# commu.net
KiCad netlist of a schematic drawn in Altium Designer
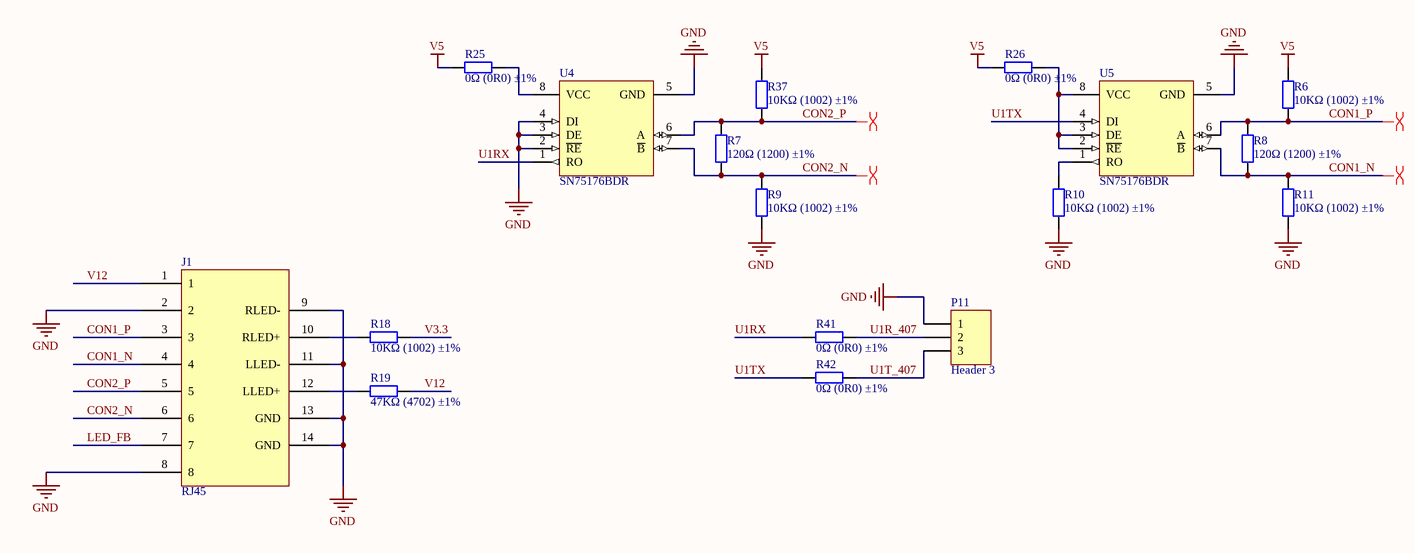
[diagram p0: commu.SchDoc]

(export (version "E")
  (design (tool "Eeschema 10.0.6"))
  (components
    (comp (ref "J1") (value "RJ45") (footprint "RJ45_1") (libsource (lib "CHK-I") (part "RJ45_1")))
    (comp (ref "P11")
      (value "Header 3")
      (footprint "HDR1X3")
      (description "Header, 3-Pin")
      (fields (field (name "PUBLISHER") "Altium Limited"))
      (libsource (lib "Miscellaneous Connectors") (part "Header 3"))
    )
    (comp (ref "R6")
      (value "10KΩ (1002) ±1%")
      (footprint "0603_R")
      (description "贴片电阻")
      (libsource (lib "Miscellaneous Devices LC") (part "0603 10KΩ (1002) 1%"))
    )
    (comp (ref "R7")
      (value "120Ω (1200) ±1%")
      (footprint "0603_R")
      (description "贴片电阻")
      (libsource (lib "Miscellaneous Devices LC") (part "0603 120Ω (1200) 1%"))
    )
    (comp (ref "R8")
      (value "120Ω (1200) ±1%")
      (footprint "0603_R")
      (description "贴片电阻")
      (libsource (lib "Miscellaneous Devices LC") (part "0603 120Ω (1200) 1%"))
    )
    (comp (ref "R9")
      (value "10KΩ (1002) ±1%")
      (footprint "0603_R")
      (description "贴片电阻")
      (libsource (lib "Miscellaneous Devices LC") (part "0603 10KΩ (1002) 1%"))
    )
    (comp (ref "R10")
      (value "10KΩ (1002) ±1%")
      (footprint "0603_R")
      (description "贴片电阻")
      (libsource (lib "Miscellaneous Devices LC") (part "0603 10KΩ (1002) 1%"))
    )
    (comp (ref "R11")
      (value "10KΩ (1002) ±1%")
      (footprint "0603_R")
      (description "贴片电阻")
      (libsource (lib "Miscellaneous Devices LC") (part "0603 10KΩ (1002) 1%"))
    )
    (comp (ref "R18")
      (value "10KΩ (1002) ±1%")
      (footprint "0603_R")
      (description "贴片电阻")
      (libsource (lib "") (part "0603 10KΩ (1002) 1%_1"))
    )
    (comp (ref "R19")
      (value "47KΩ (4702) ±1%")
      (footprint "0603_R")
      (description "贴片电阻")
      (libsource (lib "Miscellaneous Devices LC") (part "0603 47KΩ (4702) 1%"))
    )
    (comp (ref "R25")
      (value "0Ω (0R0) ±1%")
      (footprint "1206_R")
      (description "贴片电阻")
      (libsource (lib "Miscellaneous Devices LC") (part "1206 0Ω (0R0) 1%"))
    )
    (comp (ref "R26")
      (value "0Ω (0R0) ±1%")
      (footprint "1206_R")
      (description "贴片电阻")
      (libsource (lib "Miscellaneous Devices LC") (part "1206 0Ω (0R0) 1%"))
    )
    (comp (ref "R37")
      (value "10KΩ (1002) ±1%")
      (footprint "0603_R")
      (description "贴片电阻")
      (libsource (lib "Miscellaneous Devices LC") (part "0603 10KΩ (1002) 1%"))
    )
    (comp (ref "R41")
      (value "0Ω (0R0) ±1%")
      (footprint "0603_R")
      (description "贴片电阻")
      (libsource (lib "Miscellaneous Devices LC") (part "0603 0Ω (0R0) 1%"))
    )
    (comp (ref "R42")
      (value "0Ω (0R0) ±1%")
      (footprint "0603_R")
      (description "贴片电阻")
      (libsource (lib "Miscellaneous Devices LC") (part "0603 0Ω (0R0) 1%"))
    )
    (comp (ref "U4")
      (value "SN75176BDR")
      (footprint "SOIC-8_150mil")
      (description "RS-485/RS-422")
      (libsource (lib "Miscellaneous Devices LC") (part "SN75176BDR_[C7063]"))
    )
    (comp (ref "U5")
      (value "SN75176BDR")
      (footprint "SOIC-8_150mil")
      (description "RS-485/RS-422")
      (libsource (lib "Miscellaneous Devices LC") (part "SN75176BDR_[C7063]"))
    )
  )
  (nets
    (net (code "1") (name "/CON1_N") (class "Default")
      (node (ref "J1") (pin "4") (pinfunction "4_4") (pintype "passive"))
      (node (ref "R11") (pin "2") (pinfunction "2_2") (pintype "passive"))
      (node (ref "R8") (pin "1") (pinfunction "1_1") (pintype "passive"))
      (node (ref "U5") (pin "7") (pinfunction "~{B}_7") (pintype "bidirectional"))
    )
    (net (code "2") (name "/CON1_P") (class "Default")
      (node (ref "J1") (pin "3") (pinfunction "3_3") (pintype "passive"))
      (node (ref "R6") (pin "1") (pinfunction "1_1") (pintype "passive"))
      (node (ref "R8") (pin "2") (pinfunction "2_2") (pintype "passive"))
      (node (ref "U5") (pin "6") (pinfunction "A_6") (pintype "bidirectional"))
    )
    (net (code "3") (name "/CON2_N") (class "Default")
      (node (ref "J1") (pin "6") (pinfunction "6_6") (pintype "passive"))
      (node (ref "R7") (pin "1") (pinfunction "1_1") (pintype "passive"))
      (node (ref "R9") (pin "2") (pinfunction "2_2") (pintype "passive"))
      (node (ref "U4") (pin "7") (pinfunction "~{B}_7") (pintype "bidirectional"))
    )
    (net (code "4") (name "/CON2_P") (class "Default")
      (node (ref "J1") (pin "5") (pinfunction "5_5") (pintype "passive"))
      (node (ref "R37") (pin "1") (pinfunction "1_1") (pintype "passive"))
      (node (ref "R7") (pin "2") (pinfunction "2_2") (pintype "passive"))
      (node (ref "U4") (pin "6") (pinfunction "A_6") (pintype "bidirectional"))
    )
    (net (code "5") (name "/LED_FB") (class "Default")
      (node (ref "J1") (pin "7") (pinfunction "7_7") (pintype "passive"))
    )
    (net (code "6") (name "/U1RX") (class "Default")
      (node (ref "R41") (pin "1") (pinfunction "1_1") (pintype "passive"))
      (node (ref "U4") (pin "1") (pinfunction "RO_1") (pintype "output"))
    )
    (net (code "7") (name "/U1R_407") (class "Default")
      (node (ref "P11") (pin "2") (pinfunction "2_2") (pintype "passive"))
      (node (ref "R41") (pin "2") (pinfunction "2_2") (pintype "passive"))
    )
    (net (code "8") (name "/U1TX") (class "Default")
      (node (ref "R42") (pin "1") (pinfunction "1_1") (pintype "passive"))
      (node (ref "U5") (pin "4") (pinfunction "DI_4") (pintype "input"))
    )
    (net (code "9") (name "/U1T_407") (class "Default")
      (node (ref "P11") (pin "3") (pinfunction "3_3") (pintype "passive"))
      (node (ref "R42") (pin "2") (pinfunction "2_2") (pintype "passive"))
    )
    (net (code "10") (name "/V3.3") (class "Default")
      (node (ref "R18") (pin "2") (pinfunction "2_2") (pintype "passive"))
    )
    (net (code "11") (name "/V12") (class "Default")
      (node (ref "J1") (pin "1") (pinfunction "1_1") (pintype "passive"))
      (node (ref "R19") (pin "2") (pinfunction "2_2") (pintype "passive"))
    )
    (net (code "12") (name "GND") (class "Default")
      (node (ref "J1") (pin "11") (pinfunction "LLED-_11") (pintype "passive"))
      (node (ref "J1") (pin "13") (pinfunction "GND_13") (pintype "passive"))
      (node (ref "J1") (pin "14") (pinfunction "GND_14") (pintype "passive"))
      (node (ref "J1") (pin "2") (pinfunction "2_2") (pintype "passive"))
      (node (ref "J1") (pin "8") (pinfunction "8_8") (pintype "passive"))
      (node (ref "J1") (pin "9") (pinfunction "RLED-_9") (pintype "passive"))
      (node (ref "P11") (pin "1") (pinfunction "1_1") (pintype "passive"))
      (node (ref "R10") (pin "1") (pinfunction "1_1") (pintype "passive"))
      (node (ref "R11") (pin "1") (pinfunction "1_1") (pintype "passive"))
      (node (ref "R9") (pin "1") (pinfunction "1_1") (pintype "passive"))
      (node (ref "U4") (pin "2") (pinfunction "~{RE}_2") (pintype "input"))
      (node (ref "U4") (pin "3") (pinfunction "DE_3") (pintype "input"))
      (node (ref "U4") (pin "4") (pinfunction "DI_4") (pintype "input"))
      (node (ref "U4") (pin "5") (pinfunction "GND_5") (pintype "power_in"))
      (node (ref "U5") (pin "5") (pinfunction "GND_5") (pintype "power_in"))
    )
    (net (code "13") (name "Net-(J1-LLED+)") (class "Default")
      (node (ref "J1") (pin "12") (pinfunction "LLED+_12") (pintype "passive"))
      (node (ref "R19") (pin "1") (pinfunction "1_1") (pintype "passive"))
    )
    (net (code "14") (name "Net-(J1-RLED+)") (class "Default")
      (node (ref "J1") (pin "10") (pinfunction "RLED+_10") (pintype "passive"))
      (node (ref "R18") (pin "1") (pinfunction "1_1") (pintype "passive"))
    )
    (net (code "15") (name "Net-(U4-VCC)") (class "Default")
      (node (ref "R25") (pin "2") (pinfunction "2_2") (pintype "passive"))
      (node (ref "U4") (pin "8") (pinfunction "VCC_8") (pintype "power_in"))
    )
    (net (code "16") (name "Net-(U5-DE)") (class "Default")
      (node (ref "R26") (pin "2") (pinfunction "2_2") (pintype "passive"))
      (node (ref "U5") (pin "2") (pinfunction "~{RE}_2") (pintype "input"))
      (node (ref "U5") (pin "3") (pinfunction "DE_3") (pintype "input"))
      (node (ref "U5") (pin "8") (pinfunction "VCC_8") (pintype "power_in"))
    )
    (net (code "17") (name "Net-(U5-RO)") (class "Default")
      (node (ref "R10") (pin "2") (pinfunction "2_2") (pintype "passive"))
      (node (ref "U5") (pin "1") (pinfunction "RO_1") (pintype "output"))
    )
    (net (code "18") (name "V5") (class "Default")
      (node (ref "R25") (pin "1") (pinfunction "1_1") (pintype "passive"))
      (node (ref "R26") (pin "1") (pinfunction "1_1") (pintype "passive"))
      (node (ref "R37") (pin "2") (pinfunction "2_2") (pintype "passive"))
      (node (ref "R6") (pin "2") (pinfunction "2_2") (pintype "passive"))
    )
  )
)
